# button.net
KiCad netlist of a schematic drawn in EAGLE
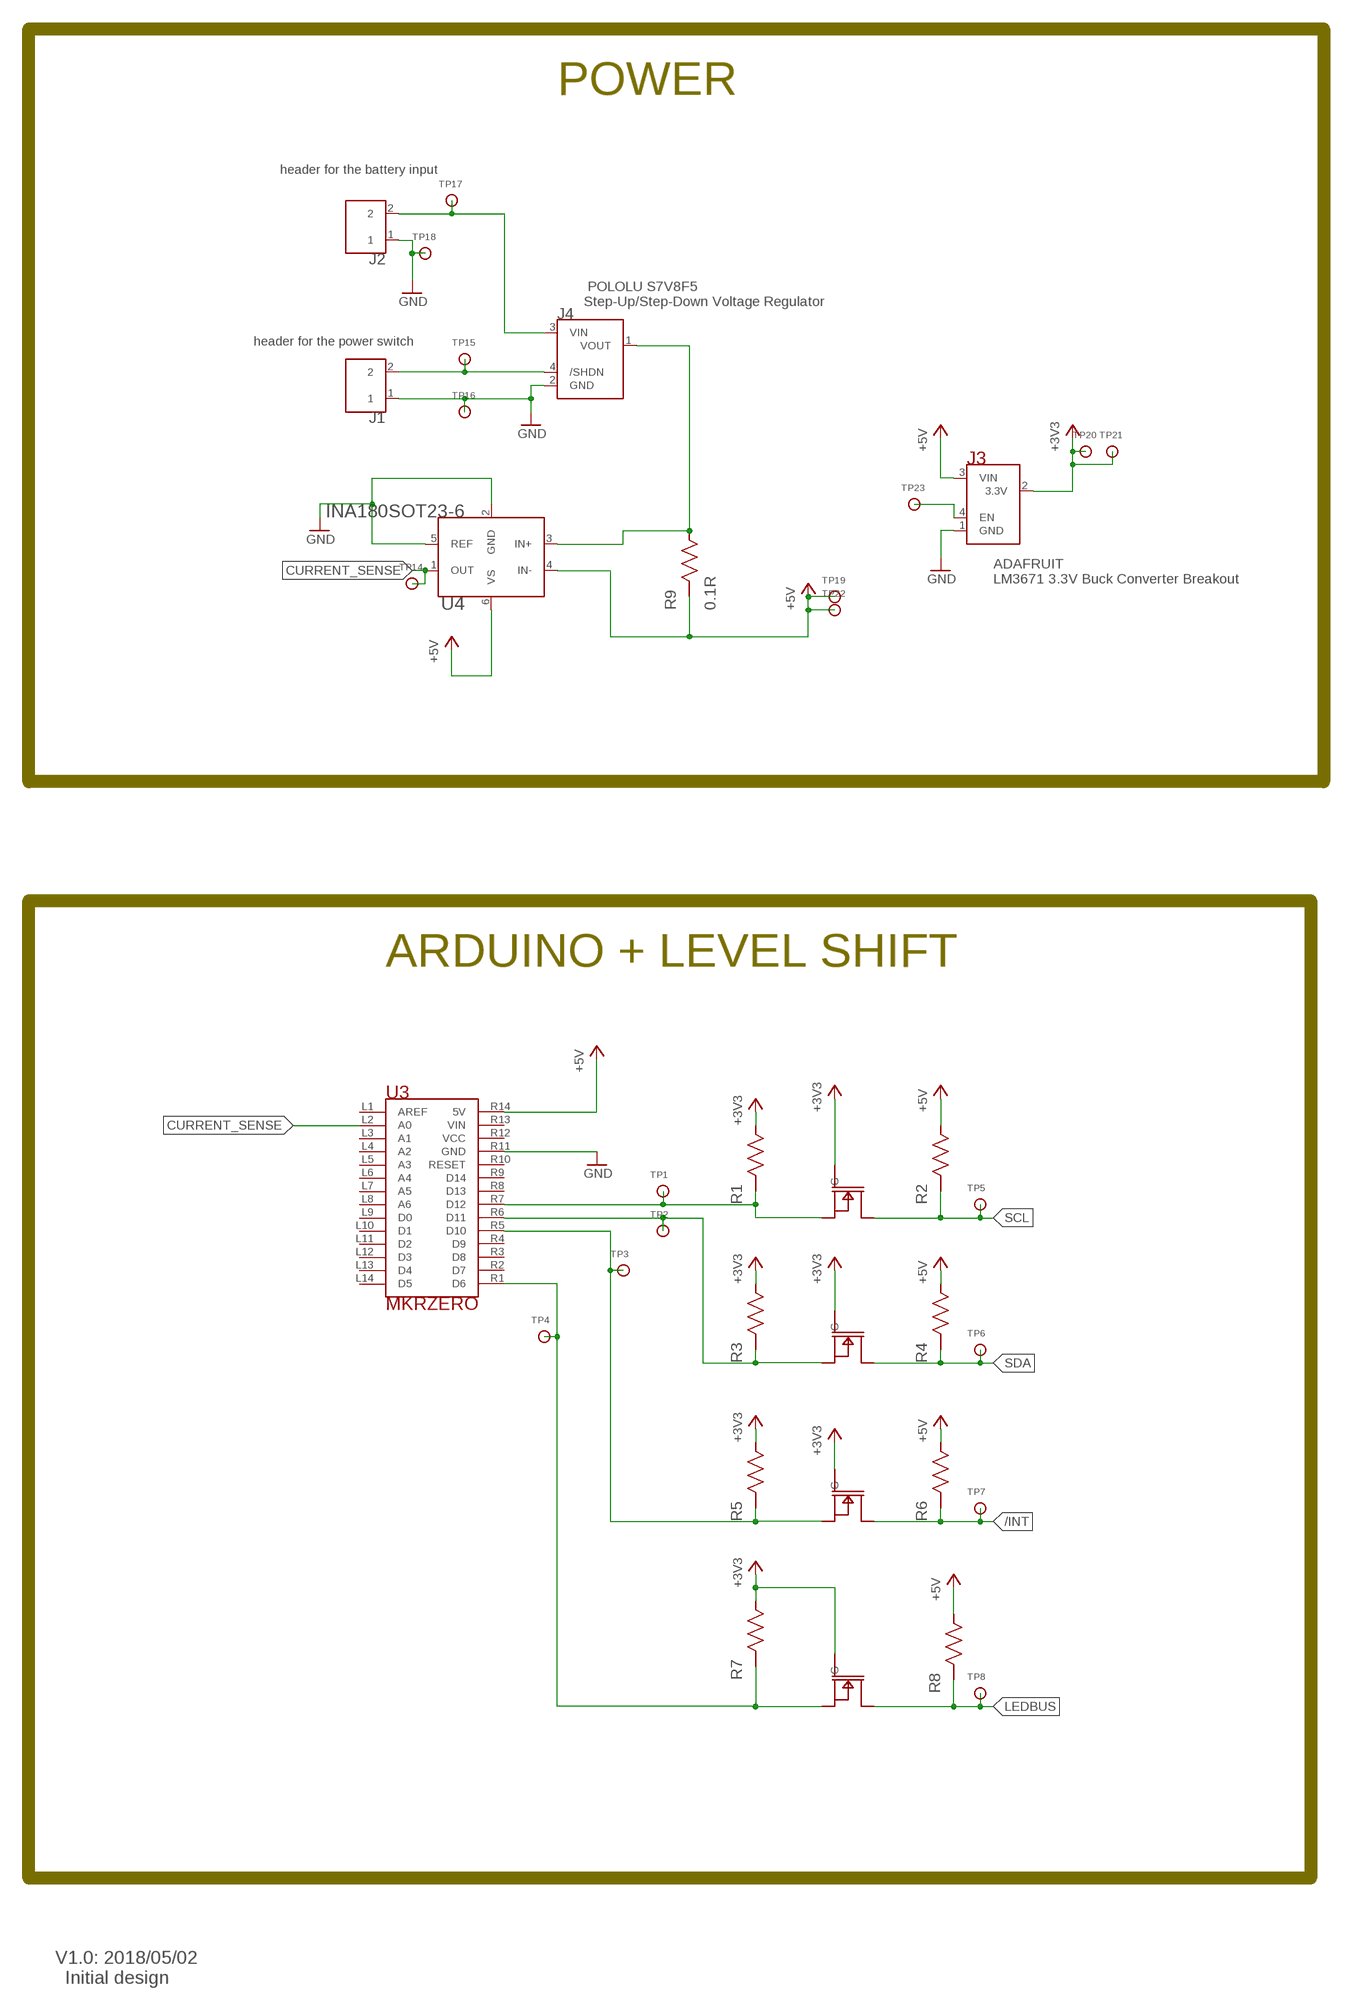
[diagram p0: schematic, sheet 1, part 1 of 2]
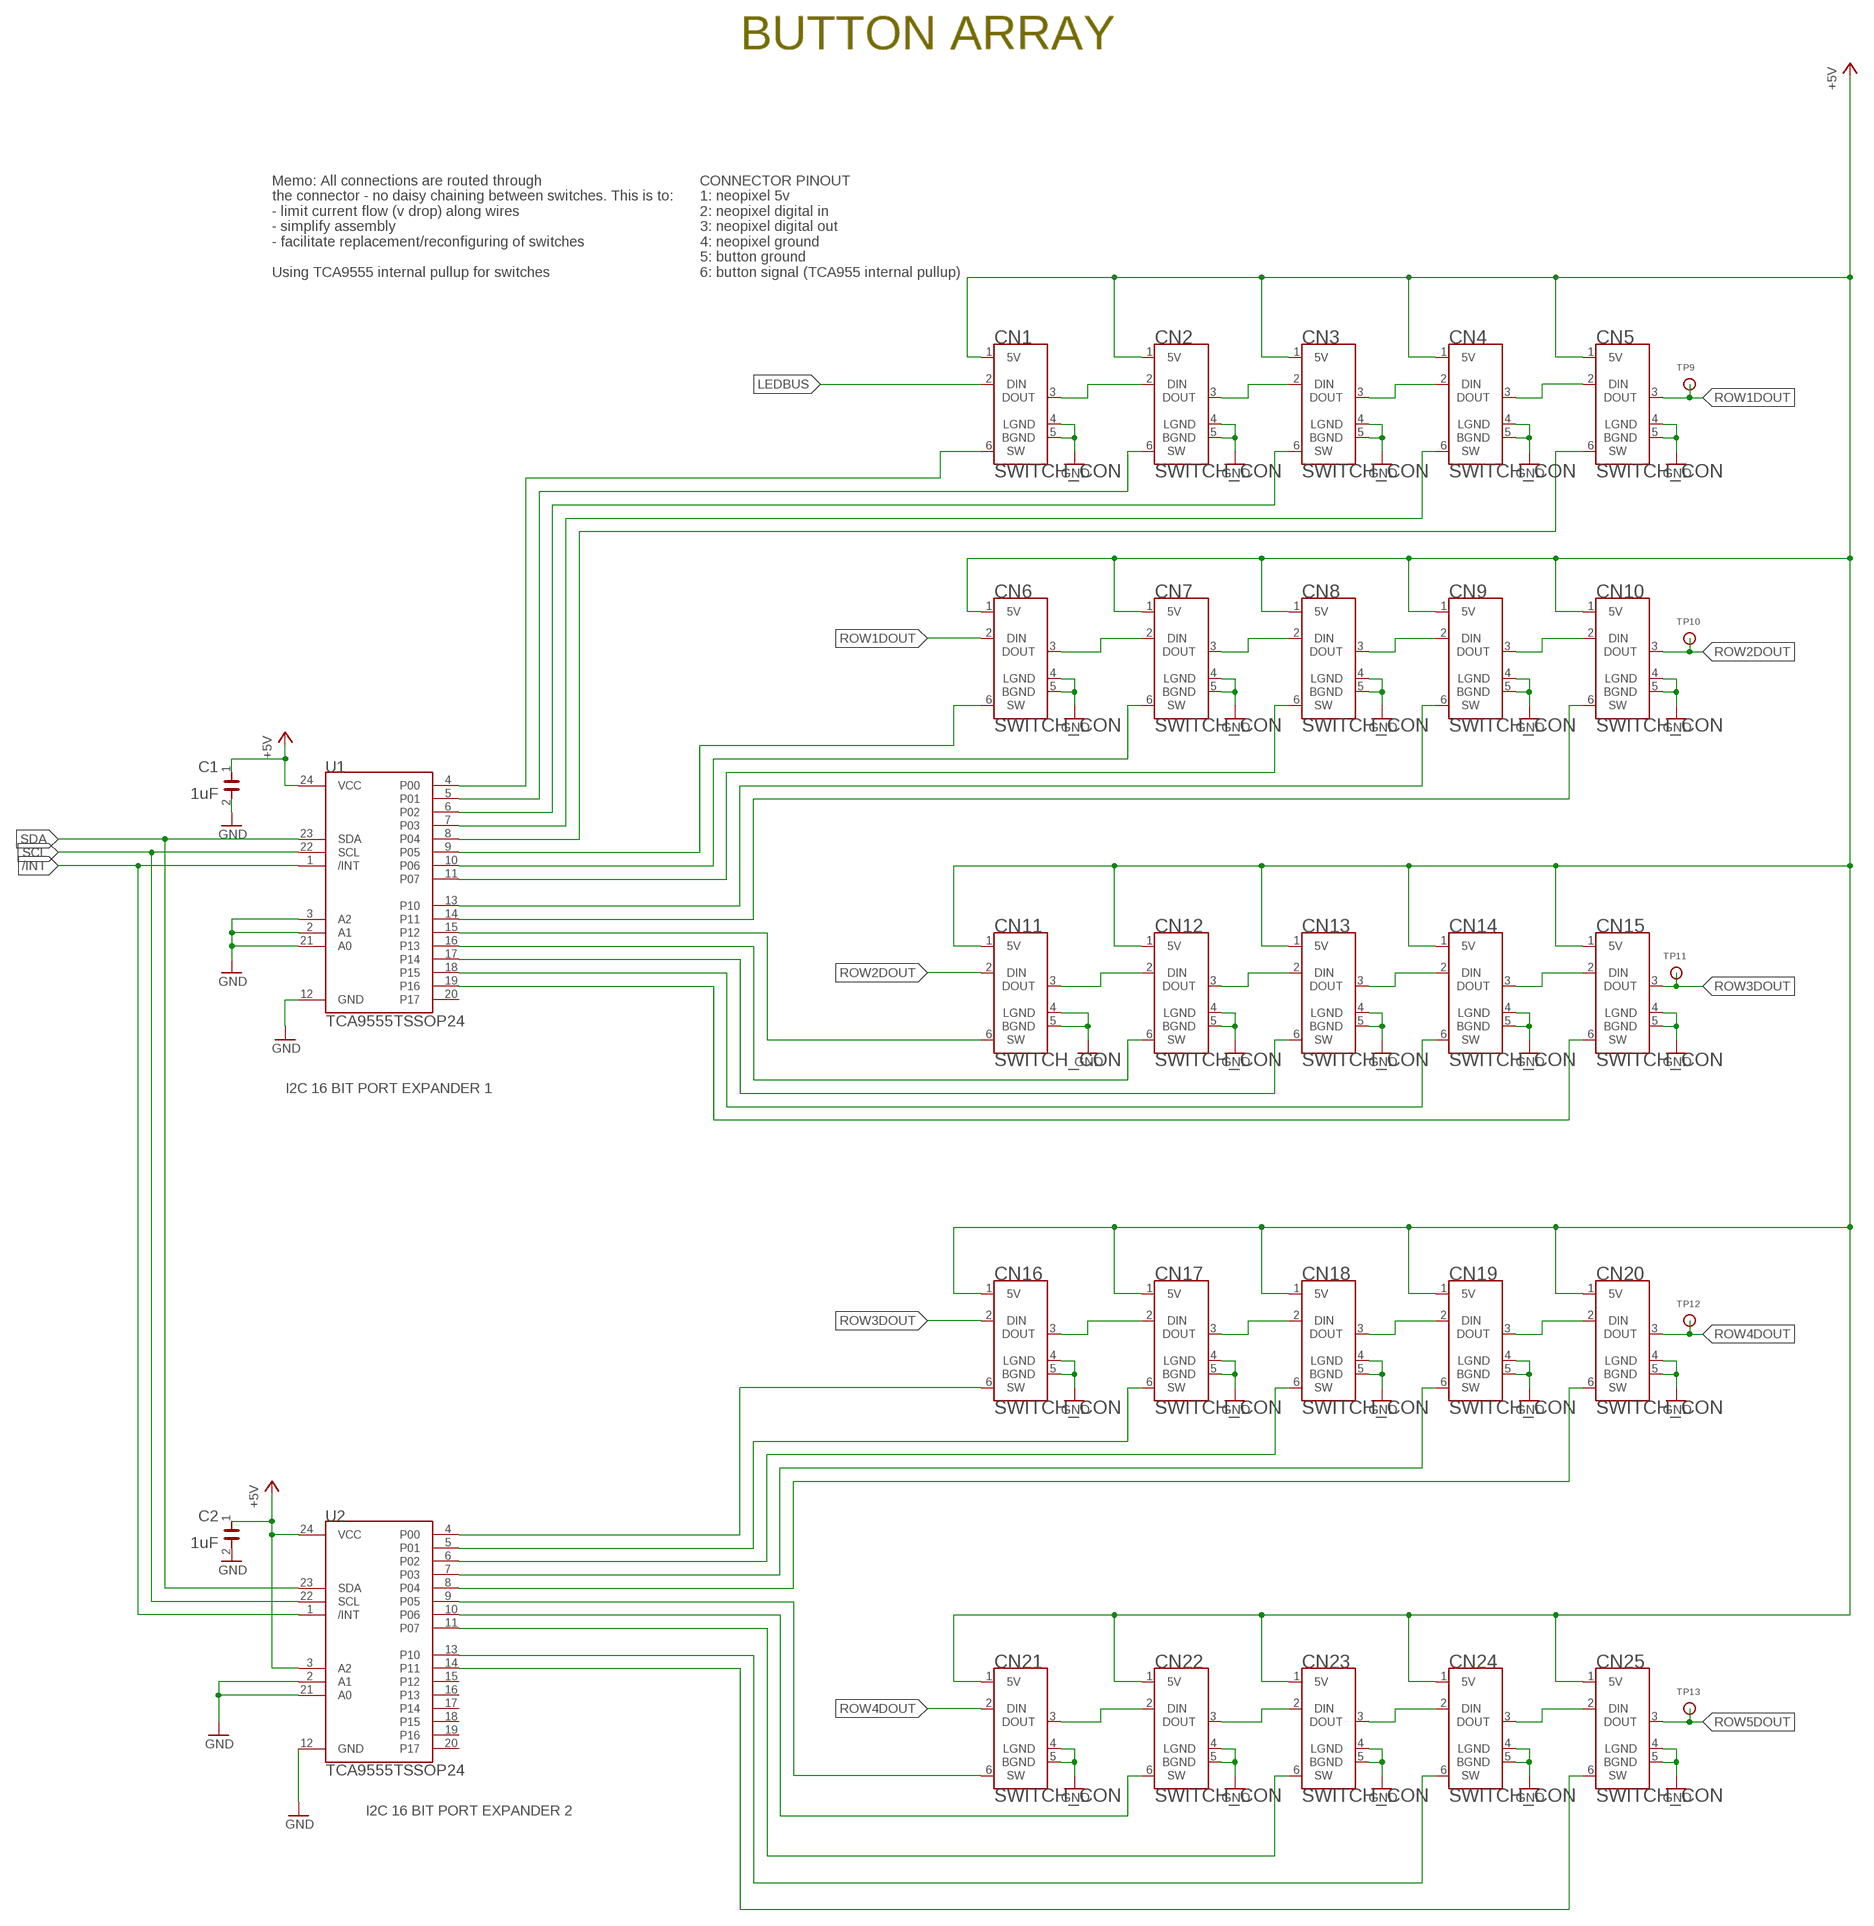
[diagram p1: schematic, sheet 1, part 2 of 2]

(export (version "E")
  (design (tool "Eeschema 10.0.6"))
  (components
    (comp (ref "C1")
      (value "1uF")
      (footprint "eagle-import:R0805")
      (libsource (lib "eagle-import") (part "CAPACITOR"))
    )
    (comp (ref "C2")
      (value "1uF")
      (footprint "eagle-import:R0805")
      (libsource (lib "eagle-import") (part "CAPACITOR"))
    )
    (comp (ref "CN1")
      (value "SWITCH_CON")
      (footprint "eagle-import:JST_XH6")
      (libsource (lib "eagle-import") (part "SWITCH_CON"))
    )
    (comp (ref "CN2")
      (value "SWITCH_CON")
      (footprint "eagle-import:JST_XH6")
      (libsource (lib "eagle-import") (part "SWITCH_CON"))
    )
    (comp (ref "CN3")
      (value "SWITCH_CON")
      (footprint "eagle-import:JST_XH6")
      (libsource (lib "eagle-import") (part "SWITCH_CON"))
    )
    (comp (ref "CN4")
      (value "SWITCH_CON")
      (footprint "eagle-import:JST_XH6")
      (libsource (lib "eagle-import") (part "SWITCH_CON"))
    )
    (comp (ref "CN5")
      (value "SWITCH_CON")
      (footprint "eagle-import:JST_XH6")
      (libsource (lib "eagle-import") (part "SWITCH_CON"))
    )
    (comp (ref "CN6")
      (value "SWITCH_CON")
      (footprint "eagle-import:JST_XH6")
      (libsource (lib "eagle-import") (part "SWITCH_CON"))
    )
    (comp (ref "CN7")
      (value "SWITCH_CON")
      (footprint "eagle-import:JST_XH6")
      (libsource (lib "eagle-import") (part "SWITCH_CON"))
    )
    (comp (ref "CN8")
      (value "SWITCH_CON")
      (footprint "eagle-import:JST_XH6")
      (libsource (lib "eagle-import") (part "SWITCH_CON"))
    )
    (comp (ref "CN9")
      (value "SWITCH_CON")
      (footprint "eagle-import:JST_XH6")
      (libsource (lib "eagle-import") (part "SWITCH_CON"))
    )
    (comp (ref "CN10")
      (value "SWITCH_CON")
      (footprint "eagle-import:JST_XH6")
      (libsource (lib "eagle-import") (part "SWITCH_CON"))
    )
    (comp (ref "CN11")
      (value "SWITCH_CON")
      (footprint "eagle-import:JST_XH6")
      (libsource (lib "eagle-import") (part "SWITCH_CON"))
    )
    (comp (ref "CN12")
      (value "SWITCH_CON")
      (footprint "eagle-import:JST_XH6")
      (libsource (lib "eagle-import") (part "SWITCH_CON"))
    )
    (comp (ref "CN13")
      (value "SWITCH_CON")
      (footprint "eagle-import:JST_XH6")
      (libsource (lib "eagle-import") (part "SWITCH_CON"))
    )
    (comp (ref "CN14")
      (value "SWITCH_CON")
      (footprint "eagle-import:JST_XH6")
      (libsource (lib "eagle-import") (part "SWITCH_CON"))
    )
    (comp (ref "CN15")
      (value "SWITCH_CON")
      (footprint "eagle-import:JST_XH6")
      (libsource (lib "eagle-import") (part "SWITCH_CON"))
    )
    (comp (ref "CN16")
      (value "SWITCH_CON")
      (footprint "eagle-import:JST_XH6")
      (libsource (lib "eagle-import") (part "SWITCH_CON"))
    )
    (comp (ref "CN17")
      (value "SWITCH_CON")
      (footprint "eagle-import:JST_XH6")
      (libsource (lib "eagle-import") (part "SWITCH_CON"))
    )
    (comp (ref "CN18")
      (value "SWITCH_CON")
      (footprint "eagle-import:JST_XH6")
      (libsource (lib "eagle-import") (part "SWITCH_CON"))
    )
    (comp (ref "CN19")
      (value "SWITCH_CON")
      (footprint "eagle-import:JST_XH6")
      (libsource (lib "eagle-import") (part "SWITCH_CON"))
    )
    (comp (ref "CN20")
      (value "SWITCH_CON")
      (footprint "eagle-import:JST_XH6")
      (libsource (lib "eagle-import") (part "SWITCH_CON"))
    )
    (comp (ref "CN21")
      (value "SWITCH_CON")
      (footprint "eagle-import:JST_XH6")
      (libsource (lib "eagle-import") (part "SWITCH_CON"))
    )
    (comp (ref "CN22")
      (value "SWITCH_CON")
      (footprint "eagle-import:JST_XH6")
      (libsource (lib "eagle-import") (part "SWITCH_CON"))
    )
    (comp (ref "CN23")
      (value "SWITCH_CON")
      (footprint "eagle-import:JST_XH6")
      (libsource (lib "eagle-import") (part "SWITCH_CON"))
    )
    (comp (ref "CN24")
      (value "SWITCH_CON")
      (footprint "eagle-import:JST_XH6")
      (libsource (lib "eagle-import") (part "SWITCH_CON"))
    )
    (comp (ref "CN25")
      (value "SWITCH_CON")
      (footprint "eagle-import:JST_XH6")
      (libsource (lib "eagle-import") (part "SWITCH_CON"))
    )
    (comp (ref "J1")
      (value "2WAY_JUMPER")
      (footprint "eagle-import:2PIN_HEADER")
      (libsource (lib "eagle-import") (part "2WAY_JUMPER"))
    )
    (comp (ref "J2")
      (value "2WAY_JUMPER")
      (footprint "eagle-import:2PIN_HEADER")
      (libsource (lib "eagle-import") (part "2WAY_JUMPER"))
    )
    (comp (ref "J3")
      (value "ADA-2745_3V3REG")
      (footprint "eagle-import:4PIN_HEADER")
      (libsource (lib "eagle-import") (part "ADA-2745_3V3REG"))
    )
    (comp (ref "J4")
      (value "S7V8F5")
      (footprint "eagle-import:4PIN_HEADER")
      (libsource (lib "eagle-import") (part "S7V8F5"))
    )
    (comp (ref "Q1")
      (value "BSS138SOT23")
      (footprint "eagle-import:SOT23")
      (libsource (lib "eagle-import") (part "BSS138SOT23"))
    )
    (comp (ref "Q2")
      (value "BSS138SOT23")
      (footprint "eagle-import:SOT23")
      (libsource (lib "eagle-import") (part "BSS138SOT23"))
    )
    (comp (ref "Q3")
      (value "BSS138SOT23")
      (footprint "eagle-import:SOT23")
      (libsource (lib "eagle-import") (part "BSS138SOT23"))
    )
    (comp (ref "Q4")
      (value "BSS138SOT23")
      (footprint "eagle-import:SOT23")
      (libsource (lib "eagle-import") (part "BSS138SOT23"))
    )
    (comp (ref "R1")
      (value "RESISTOR8085")
      (footprint "eagle-import:R0805")
      (libsource (lib "eagle-import") (part "RESISTOR8085"))
    )
    (comp (ref "R2")
      (value "RESISTOR8085")
      (footprint "eagle-import:R0805")
      (libsource (lib "eagle-import") (part "RESISTOR8085"))
    )
    (comp (ref "R3")
      (value "RESISTOR8085")
      (footprint "eagle-import:R0805")
      (libsource (lib "eagle-import") (part "RESISTOR8085"))
    )
    (comp (ref "R4")
      (value "RESISTOR8085")
      (footprint "eagle-import:R0805")
      (libsource (lib "eagle-import") (part "RESISTOR8085"))
    )
    (comp (ref "R5")
      (value "RESISTOR8085")
      (footprint "eagle-import:R0805")
      (libsource (lib "eagle-import") (part "RESISTOR8085"))
    )
    (comp (ref "R6")
      (value "RESISTOR8085")
      (footprint "eagle-import:R0805")
      (libsource (lib "eagle-import") (part "RESISTOR8085"))
    )
    (comp (ref "R7")
      (value "RESISTOR8085")
      (footprint "eagle-import:R0805")
      (libsource (lib "eagle-import") (part "RESISTOR8085"))
    )
    (comp (ref "R8")
      (value "RESISTOR8085")
      (footprint "eagle-import:R0805")
      (libsource (lib "eagle-import") (part "RESISTOR8085"))
    )
    (comp (ref "R9")
      (value "0.1R")
      (footprint "eagle-import:R1206")
      (libsource (lib "eagle-import") (part "PT1206FR-070R1L1206"))
    )
    (comp (ref "TP1")
      (value "TEST_POINT")
      (footprint "eagle-import:TESTPAD_2MM")
      (libsource (lib "eagle-import") (part "TEST_POINT"))
    )
    (comp (ref "TP2")
      (value "TEST_POINT")
      (footprint "eagle-import:TESTPAD_2MM")
      (libsource (lib "eagle-import") (part "TEST_POINT"))
    )
    (comp (ref "TP3")
      (value "TEST_POINT")
      (footprint "eagle-import:TESTPAD_2MM")
      (libsource (lib "eagle-import") (part "TEST_POINT"))
    )
    (comp (ref "TP4")
      (value "TEST_POINT")
      (footprint "eagle-import:TESTPAD_2MM")
      (libsource (lib "eagle-import") (part "TEST_POINT"))
    )
    (comp (ref "TP5")
      (value "TEST_POINT")
      (footprint "eagle-import:TESTPAD_2MM")
      (libsource (lib "eagle-import") (part "TEST_POINT"))
    )
    (comp (ref "TP6")
      (value "TEST_POINT")
      (footprint "eagle-import:TESTPAD_2MM")
      (libsource (lib "eagle-import") (part "TEST_POINT"))
    )
    (comp (ref "TP7")
      (value "TEST_POINT")
      (footprint "eagle-import:TESTPAD_2MM")
      (libsource (lib "eagle-import") (part "TEST_POINT"))
    )
    (comp (ref "TP8")
      (value "TEST_POINT")
      (footprint "eagle-import:TESTPAD_2MM")
      (libsource (lib "eagle-import") (part "TEST_POINT"))
    )
    (comp (ref "TP9")
      (value "TEST_POINT")
      (footprint "eagle-import:TESTPAD_2MM")
      (libsource (lib "eagle-import") (part "TEST_POINT"))
    )
    (comp (ref "TP10")
      (value "TEST_POINT")
      (footprint "eagle-import:TESTPAD_2MM")
      (libsource (lib "eagle-import") (part "TEST_POINT"))
    )
    (comp (ref "TP11")
      (value "TEST_POINT")
      (footprint "eagle-import:TESTPAD_2MM")
      (libsource (lib "eagle-import") (part "TEST_POINT"))
    )
    (comp (ref "TP12")
      (value "TEST_POINT")
      (footprint "eagle-import:TESTPAD_2MM")
      (libsource (lib "eagle-import") (part "TEST_POINT"))
    )
    (comp (ref "TP13")
      (value "TEST_POINT")
      (footprint "eagle-import:TESTPAD_2MM")
      (libsource (lib "eagle-import") (part "TEST_POINT"))
    )
    (comp (ref "TP14")
      (value "TEST_POINT")
      (footprint "eagle-import:TESTPAD_2MM")
      (libsource (lib "eagle-import") (part "TEST_POINT"))
    )
    (comp (ref "TP15")
      (value "TEST_POINT")
      (footprint "eagle-import:TESTPAD_2MM")
      (libsource (lib "eagle-import") (part "TEST_POINT"))
    )
    (comp (ref "TP16")
      (value "TEST_POINT")
      (footprint "eagle-import:TESTPAD_2MM")
      (libsource (lib "eagle-import") (part "TEST_POINT"))
    )
    (comp (ref "TP17")
      (value "TEST_POINT")
      (footprint "eagle-import:TESTPAD_2MM")
      (libsource (lib "eagle-import") (part "TEST_POINT"))
    )
    (comp (ref "TP18")
      (value "TEST_POINT")
      (footprint "eagle-import:TESTPAD_2MM")
      (libsource (lib "eagle-import") (part "TEST_POINT"))
    )
    (comp (ref "TP19")
      (value "TEST_POINT")
      (footprint "eagle-import:TESTPAD_2MM")
      (libsource (lib "eagle-import") (part "TEST_POINT"))
    )
    (comp (ref "TP20")
      (value "TEST_POINT")
      (footprint "eagle-import:TESTPAD_2MM")
      (libsource (lib "eagle-import") (part "TEST_POINT"))
    )
    (comp (ref "TP21")
      (value "TEST_POINT")
      (footprint "eagle-import:TESTPAD_2MM")
      (libsource (lib "eagle-import") (part "TEST_POINT"))
    )
    (comp (ref "TP22")
      (value "TEST_POINT")
      (footprint "eagle-import:TESTPAD_2MM")
      (libsource (lib "eagle-import") (part "TEST_POINT"))
    )
    (comp (ref "TP23")
      (value "TEST_POINT")
      (footprint "eagle-import:TESTPAD_2MM")
      (libsource (lib "eagle-import") (part "TEST_POINT"))
    )
    (comp (ref "U1")
      (value "TCA9555TSSOP24")
      (footprint "eagle-import:SOP65P640X120-24")
      (libsource (lib "eagle-import") (part "TCA9555TSSOP24"))
    )
    (comp (ref "U2")
      (value "TCA9555TSSOP24")
      (footprint "eagle-import:SOP65P640X120-24")
      (libsource (lib "eagle-import") (part "TCA9555TSSOP24"))
    )
    (comp (ref "U3")
      (value "MKRZERO")
      (footprint "eagle-import:ARDUINO_MKR")
      (libsource (lib "eagle-import") (part "ATMEL_MLRZERO"))
    )
    (comp (ref "U4")
      (value "INA180SOT23-6")
      (footprint "eagle-import:SOT95P290X145-6")
      (libsource (lib "eagle-import") (part "INA180SOT23-6"))
    )
  )
  (nets
    (net (code "1") (name "+3V3") (class "Default")
      (node (ref "J3") (pin "2") (pinfunction "3.3V_2") (pintype "bidirectional"))
      (node (ref "Q1") (pin "1") (pinfunction "G_1") (pintype "bidirectional"))
      (node (ref "Q2") (pin "1") (pinfunction "G_1") (pintype "bidirectional"))
      (node (ref "Q3") (pin "1") (pinfunction "G_1") (pintype "bidirectional"))
      (node (ref "Q4") (pin "1") (pinfunction "G_1") (pintype "bidirectional"))
      (node (ref "R1") (pin "2") (pinfunction "P$2_2") (pintype "bidirectional"))
      (node (ref "R3") (pin "2") (pinfunction "P$2_2") (pintype "bidirectional"))
      (node (ref "R5") (pin "2") (pinfunction "P$2_2") (pintype "bidirectional"))
      (node (ref "R7") (pin "2") (pinfunction "P$2_2") (pintype "bidirectional"))
      (node (ref "TP20") (pin "P$1") (pinfunction "1_P$1") (pintype "bidirectional"))
      (node (ref "TP21") (pin "P$1") (pinfunction "1_P$1") (pintype "bidirectional"))
    )
    (net (code "2") (name "+5V") (class "Default")
      (node (ref "C1") (pin "1") (pinfunction "P$1_1") (pintype "bidirectional"))
      (node (ref "C2") (pin "1") (pinfunction "P$1_1") (pintype "bidirectional"))
      (node (ref "CN1") (pin "1") (pinfunction "5V_1") (pintype "bidirectional"))
      (node (ref "CN10") (pin "1") (pinfunction "5V_1") (pintype "bidirectional"))
      (node (ref "CN11") (pin "1") (pinfunction "5V_1") (pintype "bidirectional"))
      (node (ref "CN12") (pin "1") (pinfunction "5V_1") (pintype "bidirectional"))
      (node (ref "CN13") (pin "1") (pinfunction "5V_1") (pintype "bidirectional"))
      (node (ref "CN14") (pin "1") (pinfunction "5V_1") (pintype "bidirectional"))
      (node (ref "CN15") (pin "1") (pinfunction "5V_1") (pintype "bidirectional"))
      (node (ref "CN16") (pin "1") (pinfunction "5V_1") (pintype "bidirectional"))
      (node (ref "CN17") (pin "1") (pinfunction "5V_1") (pintype "bidirectional"))
      (node (ref "CN18") (pin "1") (pinfunction "5V_1") (pintype "bidirectional"))
      (node (ref "CN19") (pin "1") (pinfunction "5V_1") (pintype "bidirectional"))
      (node (ref "CN2") (pin "1") (pinfunction "5V_1") (pintype "bidirectional"))
      (node (ref "CN20") (pin "1") (pinfunction "5V_1") (pintype "bidirectional"))
      (node (ref "CN21") (pin "1") (pinfunction "5V_1") (pintype "bidirectional"))
      (node (ref "CN22") (pin "1") (pinfunction "5V_1") (pintype "bidirectional"))
      (node (ref "CN23") (pin "1") (pinfunction "5V_1") (pintype "bidirectional"))
      (node (ref "CN24") (pin "1") (pinfunction "5V_1") (pintype "bidirectional"))
      (node (ref "CN25") (pin "1") (pinfunction "5V_1") (pintype "bidirectional"))
      (node (ref "CN3") (pin "1") (pinfunction "5V_1") (pintype "bidirectional"))
      (node (ref "CN4") (pin "1") (pinfunction "5V_1") (pintype "bidirectional"))
      (node (ref "CN5") (pin "1") (pinfunction "5V_1") (pintype "bidirectional"))
      (node (ref "CN6") (pin "1") (pinfunction "5V_1") (pintype "bidirectional"))
      (node (ref "CN7") (pin "1") (pinfunction "5V_1") (pintype "bidirectional"))
      (node (ref "CN8") (pin "1") (pinfunction "5V_1") (pintype "bidirectional"))
      (node (ref "CN9") (pin "1") (pinfunction "5V_1") (pintype "bidirectional"))
      (node (ref "J3") (pin "3") (pinfunction "VIN_3") (pintype "bidirectional"))
      (node (ref "R2") (pin "2") (pinfunction "P$2_2") (pintype "bidirectional"))
      (node (ref "R4") (pin "2") (pinfunction "P$2_2") (pintype "bidirectional"))
      (node (ref "R6") (pin "2") (pinfunction "P$2_2") (pintype "bidirectional"))
      (node (ref "R8") (pin "2") (pinfunction "P$2_2") (pintype "bidirectional"))
      (node (ref "R9") (pin "1") (pinfunction "P$1_1") (pintype "bidirectional"))
      (node (ref "TP19") (pin "P$1") (pinfunction "1_P$1") (pintype "bidirectional"))
      (node (ref "TP22") (pin "P$1") (pinfunction "1_P$1") (pintype "bidirectional"))
      (node (ref "U1") (pin "24") (pinfunction "VCC_24") (pintype "bidirectional"))
      (node (ref "U2") (pin "24") (pinfunction "VCC_24") (pintype "bidirectional"))
      (node (ref "U2") (pin "3") (pinfunction "A2_3") (pintype "bidirectional"))
      (node (ref "U3") (pin "R14") (pinfunction "5V_R14") (pintype "bidirectional"))
      (node (ref "U4") (pin "4") (pinfunction "IN-_4") (pintype "bidirectional"))
      (node (ref "U4") (pin "6") (pinfunction "VS_6") (pintype "power_in"))
    )
    (net (code "3") (name "CURRENT_SENSE") (class "Default")
      (node (ref "TP14") (pin "P$1") (pinfunction "1_P$1") (pintype "bidirectional"))
      (node (ref "U3") (pin "L2") (pinfunction "A0_L2") (pintype "bidirectional"))
      (node (ref "U4") (pin "1") (pinfunction "OUT_1") (pintype "bidirectional"))
    )
    (net (code "4") (name "GND") (class "Default")
      (node (ref "C1") (pin "2") (pinfunction "P$2_2") (pintype "bidirectional"))
      (node (ref "C2") (pin "2") (pinfunction "P$2_2") (pintype "bidirectional"))
      (node (ref "CN1") (pin "4") (pinfunction "LGND_4") (pintype "bidirectional"))
      (node (ref "CN1") (pin "5") (pinfunction "BGND_5") (pintype "bidirectional"))
      (node (ref "CN10") (pin "4") (pinfunction "LGND_4") (pintype "bidirectional"))
      (node (ref "CN10") (pin "5") (pinfunction "BGND_5") (pintype "bidirectional"))
      (node (ref "CN11") (pin "4") (pinfunction "LGND_4") (pintype "bidirectional"))
      (node (ref "CN11") (pin "5") (pinfunction "BGND_5") (pintype "bidirectional"))
      (node (ref "CN12") (pin "4") (pinfunction "LGND_4") (pintype "bidirectional"))
      (node (ref "CN12") (pin "5") (pinfunction "BGND_5") (pintype "bidirectional"))
      (node (ref "CN13") (pin "4") (pinfunction "LGND_4") (pintype "bidirectional"))
      (node (ref "CN13") (pin "5") (pinfunction "BGND_5") (pintype "bidirectional"))
      (node (ref "CN14") (pin "4") (pinfunction "LGND_4") (pintype "bidirectional"))
      (node (ref "CN14") (pin "5") (pinfunction "BGND_5") (pintype "bidirectional"))
      (node (ref "CN15") (pin "4") (pinfunction "LGND_4") (pintype "bidirectional"))
      (node (ref "CN15") (pin "5") (pinfunction "BGND_5") (pintype "bidirectional"))
      (node (ref "CN16") (pin "4") (pinfunction "LGND_4") (pintype "bidirectional"))
      (node (ref "CN16") (pin "5") (pinfunction "BGND_5") (pintype "bidirectional"))
      (node (ref "CN17") (pin "4") (pinfunction "LGND_4") (pintype "bidirectional"))
      (node (ref "CN17") (pin "5") (pinfunction "BGND_5") (pintype "bidirectional"))
      (node (ref "CN18") (pin "4") (pinfunction "LGND_4") (pintype "bidirectional"))
      (node (ref "CN18") (pin "5") (pinfunction "BGND_5") (pintype "bidirectional"))
      (node (ref "CN19") (pin "4") (pinfunction "LGND_4") (pintype "bidirectional"))
      (node (ref "CN19") (pin "5") (pinfunction "BGND_5") (pintype "bidirectional"))
      (node (ref "CN2") (pin "4") (pinfunction "LGND_4") (pintype "bidirectional"))
      (node (ref "CN2") (pin "5") (pinfunction "BGND_5") (pintype "bidirectional"))
      (node (ref "CN20") (pin "4") (pinfunction "LGND_4") (pintype "bidirectional"))
      (node (ref "CN20") (pin "5") (pinfunction "BGND_5") (pintype "bidirectional"))
      (node (ref "CN21") (pin "4") (pinfunction "LGND_4") (pintype "bidirectional"))
      (node (ref "CN21") (pin "5") (pinfunction "BGND_5") (pintype "bidirectional"))
      (node (ref "CN22") (pin "4") (pinfunction "LGND_4") (pintype "bidirectional"))
      (node (ref "CN22") (pin "5") (pinfunction "BGND_5") (pintype "bidirectional"))
      (node (ref "CN23") (pin "4") (pinfunction "LGND_4") (pintype "bidirectional"))
      (node (ref "CN23") (pin "5") (pinfunction "BGND_5") (pintype "bidirectional"))
      (node (ref "CN24") (pin "4") (pinfunction "LGND_4") (pintype "bidirectional"))
      (node (ref "CN24") (pin "5") (pinfunction "BGND_5") (pintype "bidirectional"))
      (node (ref "CN25") (pin "4") (pinfunction "LGND_4") (pintype "bidirectional"))
      (node (ref "CN25") (pin "5") (pinfunction "BGND_5") (pintype "bidirectional"))
      (node (ref "CN3") (pin "4") (pinfunction "LGND_4") (pintype "bidirectional"))
      (node (ref "CN3") (pin "5") (pinfunction "BGND_5") (pintype "bidirectional"))
      (node (ref "CN4") (pin "4") (pinfunction "LGND_4") (pintype "bidirectional"))
      (node (ref "CN4") (pin "5") (pinfunction "BGND_5") (pintype "bidirectional"))
      (node (ref "CN5") (pin "4") (pinfunction "LGND_4") (pintype "bidirectional"))
      (node (ref "CN5") (pin "5") (pinfunction "BGND_5") (pintype "bidirectional"))
      (node (ref "CN6") (pin "4") (pinfunction "LGND_4") (pintype "bidirectional"))
      (node (ref "CN6") (pin "5") (pinfunction "BGND_5") (pintype "bidirectional"))
      (node (ref "CN7") (pin "4") (pinfunction "LGND_4") (pintype "bidirectional"))
      (node (ref "CN7") (pin "5") (pinfunction "BGND_5") (pintype "bidirectional"))
      (node (ref "CN8") (pin "4") (pinfunction "LGND_4") (pintype "bidirectional"))
      (node (ref "CN8") (pin "5") (pinfunction "BGND_5") (pintype "bidirectional"))
      (node (ref "CN9") (pin "4") (pinfunction "LGND_4") (pintype "bidirectional"))
      (node (ref "CN9") (pin "5") (pinfunction "BGND_5") (pintype "bidirectional"))
      (node (ref "J1") (pin "1") (pinfunction "1_1") (pintype "bidirectional"))
      (node (ref "J2") (pin "1") (pinfunction "1_1") (pintype "bidirectional"))
      (node (ref "J3") (pin "1") (pinfunction "GND_1") (pintype "bidirectional"))
      (node (ref "J4") (pin "2") (pinfunction "GND_2") (pintype "bidirectional"))
      (node (ref "TP16") (pin "P$1") (pinfunction "1_P$1") (pintype "bidirectional"))
      (node (ref "TP18") (pin "P$1") (pinfunction "1_P$1") (pintype "bidirectional"))
      (node (ref "U1") (pin "12") (pinfunction "GND_12") (pintype "bidirectional"))
      (node (ref "U1") (pin "2") (pinfunction "A1_2") (pintype "bidirectional"))
      (node (ref "U1") (pin "21") (pinfunction "A0_21") (pintype "bidirectional"))
      (node (ref "U1") (pin "3") (pinfunction "A2_3") (pintype "bidirectional"))
      (node (ref "U2") (pin "12") (pinfunction "GND_12") (pintype "bidirectional"))
      (node (ref "U2") (pin "2") (pinfunction "A1_2") (pintype "bidirectional"))
      (node (ref "U2") (pin "21") (pinfunction "A0_21") (pintype "bidirectional"))
      (node (ref "U3") (pin "R11") (pinfunction "GND_R11") (pintype "bidirectional"))
      (node (ref "U4") (pin "2") (pinfunction "GND_2") (pintype "bidirectional"))
      (node (ref "U4") (pin "5") (pinfunction "REF_5") (pintype "bidirectional"))
    )
    (net (code "5") (name "LEDBUS") (class "Default")
      (node (ref "CN1") (pin "2") (pinfunction "DIN_2") (pintype "bidirectional"))
      (node (ref "Q4") (pin "3") (pinfunction "D_3") (pintype "bidirectional"))
      (node (ref "R8") (pin "1") (pinfunction "P$1_1") (pintype "bidirectional"))
      (node (ref "TP8") (pin "P$1") (pinfunction "1_P$1") (pintype "bidirectional"))
    )
    (net (code "6") (name "Net-(CN1-DOUT)") (class "Default")
      (node (ref "CN1") (pin "3") (pinfunction "DOUT_3") (pintype "bidirectional"))
      (node (ref "CN2") (pin "2") (pinfunction "DIN_2") (pintype "bidirectional"))
    )
    (net (code "7") (name "Net-(CN1-SW)") (class "Default")
      (node (ref "CN1") (pin "6") (pinfunction "SW_6") (pintype "bidirectional"))
      (node (ref "U1") (pin "4") (pinfunction "P00_4") (pintype "bidirectional"))
    )
    (net (code "8") (name "Net-(CN2-DOUT)") (class "Default")
      (node (ref "CN2") (pin "3") (pinfunction "DOUT_3") (pintype "bidirectional"))
      (node (ref "CN3") (pin "2") (pinfunction "DIN_2") (pintype "bidirectional"))
    )
    (net (code "9") (name "Net-(CN2-SW)") (class "Default")
      (node (ref "CN2") (pin "6") (pinfunction "SW_6") (pintype "bidirectional"))
      (node (ref "U1") (pin "5") (pinfunction "P01_5") (pintype "bidirectional"))
    )
    (net (code "10") (name "Net-(CN3-DOUT)") (class "Default")
      (node (ref "CN3") (pin "3") (pinfunction "DOUT_3") (pintype "bidirectional"))
      (node (ref "CN4") (pin "2") (pinfunction "DIN_2") (pintype "bidirectional"))
    )
    (net (code "11") (name "Net-(CN3-SW)") (class "Default")
      (node (ref "CN3") (pin "6") (pinfunction "SW_6") (pintype "bidirectional"))
      (node (ref "U1") (pin "6") (pinfunction "P02_6") (pintype "bidirectional"))
    )
    (net (code "12") (name "Net-(CN4-DOUT)") (class "Default")
      (node (ref "CN4") (pin "3") (pinfunction "DOUT_3") (pintype "bidirectional"))
      (node (ref "CN5") (pin "2") (pinfunction "DIN_2") (pintype "bidirectional"))
    )
    (net (code "13") (name "Net-(CN4-SW)") (class "Default")
      (node (ref "CN4") (pin "6") (pinfunction "SW_6") (pintype "bidirectional"))
      (node (ref "U1") (pin "7") (pinfunction "P03_7") (pintype "bidirectional"))
    )
    (net (code "14") (name "Net-(CN5-SW)") (class "Default")
      (node (ref "CN5") (pin "6") (pinfunction "SW_6") (pintype "bidirectional"))
      (node (ref "U1") (pin "8") (pinfunction "P04_8") (pintype "bidirectional"))
    )
    (net (code "15") (name "Net-(CN6-DOUT)") (class "Default")
      (node (ref "CN6") (pin "3") (pinfunction "DOUT_3") (pintype "bidirectional"))
      (node (ref "CN7") (pin "2") (pinfunction "DIN_2") (pintype "bidirectional"))
    )
    (net (code "16") (name "Net-(CN6-SW)") (class "Default")
      (node (ref "CN6") (pin "6") (pinfunction "SW_6") (pintype "bidirectional"))
      (node (ref "U1") (pin "9") (pinfunction "P05_9") (pintype "bidirectional"))
    )
    (net (code "17") (name "Net-(CN7-DOUT)") (class "Default")
      (node (ref "CN7") (pin "3") (pinfunction "DOUT_3") (pintype "bidirectional"))
      (node (ref "CN8") (pin "2") (pinfunction "DIN_2") (pintype "bidirectional"))
    )
    (net (code "18") (name "Net-(CN7-SW)") (class "Default")
      (node (ref "CN7") (pin "6") (pinfunction "SW_6") (pintype "bidirectional"))
      (node (ref "U1") (pin "10") (pinfunction "P06_10") (pintype "bidirectional"))
    )
    (net (code "19") (name "Net-(CN8-DOUT)") (class "Default")
      (node (ref "CN8") (pin "3") (pinfunction "DOUT_3") (pintype "bidirectional"))
      (node (ref "CN9") (pin "2") (pinfunction "DIN_2") (pintype "bidirectional"))
    )
    (net (code "20") (name "Net-(CN8-SW)") (class "Default")
      (node (ref "CN8") (pin "6") (pinfunction "SW_6") (pintype "bidirectional"))
      (node (ref "U1") (pin "11") (pinfunction "P07_11") (pintype "bidirectional"))
    )
    (net (code "21") (name "Net-(CN9-SW)") (class "Default")
      (node (ref "CN9") (pin "6") (pinfunction "SW_6") (pintype "bidirectional"))
      (node (ref "U1") (pin "13") (pinfunction "P10_13") (pintype "bidirectional"))
    )
    (net (code "22") (name "Net-(CN10-DIN)") (class "Default")
      (node (ref "CN10") (pin "2") (pinfunction "DIN_2") (pintype "bidirectional"))
      (node (ref "CN9") (pin "3") (pinfunction "DOUT_3") (pintype "bidirectional"))
    )
    (net (code "23") (name "Net-(CN10-SW)") (class "Default")
      (node (ref "CN10") (pin "6") (pinfunction "SW_6") (pintype "bidirectional"))
      (node (ref "U1") (pin "14") (pinfunction "P11_14") (pintype "bidirectional"))
    )
    (net (code "24") (name "Net-(CN11-DOUT)") (class "Default")
      (node (ref "CN11") (pin "3") (pinfunction "DOUT_3") (pintype "bidirectional"))
      (node (ref "CN12") (pin "2") (pinfunction "DIN_2") (pintype "bidirectional"))
    )
    (net (code "25") (name "Net-(CN11-SW)") (class "Default")
      (node (ref "CN11") (pin "6") (pinfunction "SW_6") (pintype "bidirectional"))
      (node (ref "U1") (pin "15") (pinfunction "P12_15") (pintype "bidirectional"))
    )
    (net (code "26") (name "Net-(CN12-DOUT)") (class "Default")
      (node (ref "CN12") (pin "3") (pinfunction "DOUT_3") (pintype "bidirectional"))
      (node (ref "CN13") (pin "2") (pinfunction "DIN_2") (pintype "bidirectional"))
    )
    (net (code "27") (name "Net-(CN12-SW)") (class "Default")
      (node (ref "CN12") (pin "6") (pinfunction "SW_6") (pintype "bidirectional"))
      (node (ref "U1") (pin "16") (pinfunction "P13_16") (pintype "bidirectional"))
    )
    (net (code "28") (name "Net-(CN13-DOUT)") (class "Default")
      (node (ref "CN13") (pin "3") (pinfunction "DOUT_3") (pintype "bidirectional"))
      (node (ref "CN14") (pin "2") (pinfunction "DIN_2") (pintype "bidirectional"))
    )
    (net (code "29") (name "Net-(CN13-SW)") (class "Default")
      (node (ref "CN13") (pin "6") (pinfunction "SW_6") (pintype "bidirectional"))
      (node (ref "U1") (pin "17") (pinfunction "P14_17") (pintype "bidirectional"))
    )
    (net (code "30") (name "Net-(CN14-DOUT)") (class "Default")
      (node (ref "CN14") (pin "3") (pinfunction "DOUT_3") (pintype "bidirectional"))
      (node (ref "CN15") (pin "2") (pinfunction "DIN_2") (pintype "bidirectional"))
    )
    (net (code "31") (name "Net-(CN14-SW)") (class "Default")
      (node (ref "CN14") (pin "6") (pinfunction "SW_6") (pintype "bidirectional"))
      (node (ref "U1") (pin "18") (pinfunction "P15_18") (pintype "bidirectional"))
    )
    (net (code "32") (name "Net-(CN15-SW)") (class "Default")
      (node (ref "CN15") (pin "6") (pinfunction "SW_6") (pintype "bidirectional"))
      (node (ref "U1") (pin "19") (pinfunction "P16_19") (pintype "bidirectional"))
    )
    (net (code "33") (name "Net-(CN16-DOUT)") (class "Default")
      (node (ref "CN16") (pin "3") (pinfunction "DOUT_3") (pintype "bidirectional"))
      (node (ref "CN17") (pin "2") (pinfunction "DIN_2") (pintype "bidirectional"))
    )
    (net (code "34") (name "Net-(CN16-SW)") (class "Default")
      (node (ref "CN16") (pin "6") (pinfunction "SW_6") (pintype "bidirectional"))
      (node (ref "U2") (pin "4") (pinfunction "P00_4") (pintype "bidirectional"))
    )
    (net (code "35") (name "Net-(CN17-DOUT)") (class "Default")
      (node (ref "CN17") (pin "3") (pinfunction "DOUT_3") (pintype "bidirectional"))
      (node (ref "CN18") (pin "2") (pinfunction "DIN_2") (pintype "bidirectional"))
    )
    (net (code "36") (name "Net-(CN17-SW)") (class "Default")
      (node (ref "CN17") (pin "6") (pinfunction "SW_6") (pintype "bidirectional"))
      (node (ref "U2") (pin "5") (pinfunction "P01_5") (pintype "bidirectional"))
    )
    (net (code "37") (name "Net-(CN18-DOUT)") (class "Default")
      (node (ref "CN18") (pin "3") (pinfunction "DOUT_3") (pintype "bidirectional"))
      (node (ref "CN19") (pin "2") (pinfunction "DIN_2") (pintype "bidirectional"))
    )
    (net (code "38") (name "Net-(CN18-SW)") (class "Default")
      (node (ref "CN18") (pin "6") (pinfunction "SW_6") (pintype "bidirectional"))
      (node (ref "U2") (pin "6") (pinfunction "P02_6") (pintype "bidirectional"))
    )
    (net (code "39") (name "Net-(CN19-DOUT)") (class "Default")
      (node (ref "CN19") (pin "3") (pinfunction "DOUT_3") (pintype "bidirectional"))
      (node (ref "CN20") (pin "2") (pinfunction "DIN_2") (pintype "bidirectional"))
    )
    (net (code "40") (name "Net-(CN19-SW)") (class "Default")
      (node (ref "CN19") (pin "6") (pinfunction "SW_6") (pintype "bidirectional"))
      (node (ref "U2") (pin "7") (pinfunction "P03_7") (pintype "bidirectional"))
    )
    (net (code "41") (name "Net-(CN20-SW)") (class "Default")
      (node (ref "CN20") (pin "6") (pinfunction "SW_6") (pintype "bidirectional"))
      (node (ref "U2") (pin "8") (pinfunction "P04_8") (pintype "bidirectional"))
    )
    (net (code "42") (name "Net-(CN21-DOUT)") (class "Default")
      (node (ref "CN21") (pin "3") (pinfunction "DOUT_3") (pintype "bidirectional"))
      (node (ref "CN22") (pin "2") (pinfunction "DIN_2") (pintype "bidirectional"))
    )
    (net (code "43") (name "Net-(CN21-SW)") (class "Default")
      (node (ref "CN21") (pin "6") (pinfunction "SW_6") (pintype "bidirectional"))
      (node (ref "U2") (pin "9") (pinfunction "P05_9") (pintype "bidirectional"))
    )
    (net (code "44") (name "Net-(CN22-DOUT)") (class "Default")
      (node (ref "CN22") (pin "3") (pinfunction "DOUT_3") (pintype "bidirectional"))
      (node (ref "CN23") (pin "2") (pinfunction "DIN_2") (pintype "bidirectional"))
    )
    (net (code "45") (name "Net-(CN22-SW)") (class "Default")
      (node (ref "CN22") (pin "6") (pinfunction "SW_6") (pintype "bidirectional"))
      (node (ref "U2") (pin "10") (pinfunction "P06_10") (pintype "bidirectional"))
    )
    (net (code "46") (name "Net-(CN23-DOUT)") (class "Default")
      (node (ref "CN23") (pin "3") (pinfunction "DOUT_3") (pintype "bidirectional"))
      (node (ref "CN24") (pin "2") (pinfunction "DIN_2") (pintype "bidirectional"))
    )
    (net (code "47") (name "Net-(CN23-SW)") (class "Default")
      (node (ref "CN23") (pin "6") (pinfunction "SW_6") (pintype "bidirectional"))
      (node (ref "U2") (pin "11") (pinfunction "P07_11") (pintype "bidirectional"))
    )
    (net (code "48") (name "Net-(CN24-DOUT)") (class "Default")
      (node (ref "CN24") (pin "3") (pinfunction "DOUT_3") (pintype "bidirectional"))
      (node (ref "CN25") (pin "2") (pinfunction "DIN_2") (pintype "bidirectional"))
    )
    (net (code "49") (name "Net-(CN24-SW)") (class "Default")
      (node (ref "CN24") (pin "6") (pinfunction "SW_6") (pintype "bidirectional"))
      (node (ref "U2") (pin "13") (pinfunction "P10_13") (pintype "bidirectional"))
    )
    (net (code "50") (name "Net-(CN25-SW)") (class "Default")
      (node (ref "CN25") (pin "6") (pinfunction "SW_6") (pintype "bidirectional"))
      (node (ref "U2") (pin "14") (pinfunction "P11_14") (pintype "bidirectional"))
    )
    (net (code "51") (name "Net-(J3-EN)") (class "Default")
      (node (ref "J3") (pin "4") (pinfunction "EN_4") (pintype "bidirectional"))
      (node (ref "TP23") (pin "P$1") (pinfunction "1_P$1") (pintype "bidirectional"))
    )
    (net (code "52") (name "Net-(J4-VIN)") (class "Default")
      (node (ref "J2") (pin "2") (pinfunction "2_2") (pintype "bidirectional"))
      (node (ref "J4") (pin "3") (pinfunction "VIN_3") (pintype "bidirectional"))
      (node (ref "TP17") (pin "P$1") (pinfunction "1_P$1") (pintype "bidirectional"))
    )
    (net (code "53") (name "Net-(J4-VOUT)") (class "Default")
      (node (ref "J4") (pin "1") (pinfunction "VOUT_1") (pintype "bidirectional"))
      (node (ref "R9") (pin "2") (pinfunction "P$2_2") (pintype "bidirectional"))
      (node (ref "U4") (pin "3") (pinfunction "IN+_3") (pintype "power_in"))
    )
    (net (code "54") (name "Net-(J4-{slash}SHDN)") (class "Default")
      (node (ref "J1") (pin "2") (pinfunction "2_2") (pintype "bidirectional"))
      (node (ref "J4") (pin "4") (pinfunction "/SHDN_4") (pintype "bidirectional"))
      (node (ref "TP15") (pin "P$1") (pinfunction "1_P$1") (pintype "bidirectional"))
    )
    (net (code "55") (name "Net-(Q1-S)") (class "Default")
      (node (ref "Q1") (pin "2") (pinfunction "S_2") (pintype "bidirectional"))
      (node (ref "R3") (pin "1") (pinfunction "P$1_1") (pintype "bidirectional"))
      (node (ref "TP2") (pin "P$1") (pinfunction "1_P$1") (pintype "bidirectional"))
      (node (ref "U3") (pin "R6") (pinfunction "D11_R6") (pintype "bidirectional"))
    )
    (net (code "56") (name "Net-(Q2-S)") (class "Default")
      (node (ref "Q2") (pin "2") (pinfunction "S_2") (pintype "bidirectional"))
      (node (ref "R5") (pin "1") (pinfunction "P$1_1") (pintype "bidirectional"))
      (node (ref "TP3") (pin "P$1") (pinfunction "1_P$1") (pintype "bidirectional"))
      (node (ref "U3") (pin "R5") (pinfunction "D10_R5") (pintype "bidirectional"))
    )
    (net (code "57") (name "Net-(Q3-S)") (class "Default")
      (node (ref "Q3") (pin "2") (pinfunction "S_2") (pintype "bidirectional"))
      (node (ref "R1") (pin "1") (pinfunction "P$1_1") (pintype "bidirectional"))
      (node (ref "TP1") (pin "P$1") (pinfunction "1_P$1") (pintype "bidirectional"))
      (node (ref "U3") (pin "R7") (pinfunction "D12_R7") (pintype "bidirectional"))
    )
    (net (code "58") (name "Net-(Q4-S)") (class "Default")
      (node (ref "Q4") (pin "2") (pinfunction "S_2") (pintype "bidirectional"))
      (node (ref "R7") (pin "1") (pinfunction "P$1_1") (pintype "bidirectional"))
      (node (ref "TP4") (pin "P$1") (pinfunction "1_P$1") (pintype "bidirectional"))
      (node (ref "U3") (pin "R1") (pinfunction "D6_R1") (pintype "bidirectional"))
    )
    (net (code "59") (name "ROW1DOUT") (class "Default")
      (node (ref "CN5") (pin "3") (pinfunction "DOUT_3") (pintype "bidirectional"))
      (node (ref "CN6") (pin "2") (pinfunction "DIN_2") (pintype "bidirectional"))
      (node (ref "TP9") (pin "P$1") (pinfunction "1_P$1") (pintype "bidirectional"))
    )
    (net (code "60") (name "ROW2DOUT") (class "Default")
      (node (ref "CN10") (pin "3") (pinfunction "DOUT_3") (pintype "bidirectional"))
      (node (ref "CN11") (pin "2") (pinfunction "DIN_2") (pintype "bidirectional"))
      (node (ref "TP10") (pin "P$1") (pinfunction "1_P$1") (pintype "bidirectional"))
    )
    (net (code "61") (name "ROW3DOUT") (class "Default")
      (node (ref "CN15") (pin "3") (pinfunction "DOUT_3") (pintype "bidirectional"))
      (node (ref "CN16") (pin "2") (pinfunction "DIN_2") (pintype "bidirectional"))
      (node (ref "TP11") (pin "P$1") (pinfunction "1_P$1") (pintype "bidirectional"))
    )
    (net (code "62") (name "ROW4DOUT") (class "Default")
      (node (ref "CN20") (pin "3") (pinfunction "DOUT_3") (pintype "bidirectional"))
      (node (ref "CN21") (pin "2") (pinfunction "DIN_2") (pintype "bidirectional"))
      (node (ref "TP12") (pin "P$1") (pinfunction "1_P$1") (pintype "bidirectional"))
    )
    (net (code "63") (name "ROW5DOUT") (class "Default")
      (node (ref "CN25") (pin "3") (pinfunction "DOUT_3") (pintype "bidirectional"))
      (node (ref "TP13") (pin "P$1") (pinfunction "1_P$1") (pintype "bidirectional"))
    )
    (net (code "64") (name "SCL") (class "Default")
      (node (ref "Q3") (pin "3") (pinfunction "D_3") (pintype "bidirectional"))
      (node (ref "R2") (pin "1") (pinfunction "P$1_1") (pintype "bidirectional"))
      (node (ref "TP5") (pin "P$1") (pinfunction "1_P$1") (pintype "bidirectional"))
      (node (ref "U1") (pin "22") (pinfunction "SCL_22") (pintype "bidirectional"))
      (node (ref "U2") (pin "22") (pinfunction "SCL_22") (pintype "bidirectional"))
    )
    (net (code "65") (name "SDA") (class "Default")
      (node (ref "Q1") (pin "3") (pinfunction "D_3") (pintype "bidirectional"))
      (node (ref "R4") (pin "1") (pinfunction "P$1_1") (pintype "bidirectional"))
      (node (ref "TP6") (pin "P$1") (pinfunction "1_P$1") (pintype "bidirectional"))
      (node (ref "U1") (pin "23") (pinfunction "SDA_23") (pintype "bidirectional"))
      (node (ref "U2") (pin "23") (pinfunction "SDA_23") (pintype "bidirectional"))
    )
    (net (code "66") (name "unconnected-(U1-P17-Pad20)") (class "Default")
      (node (ref "U1") (pin "20") (pinfunction "P17_20") (pintype "bidirectional"))
    )
    (net (code "67") (name "unconnected-(U2-P12-Pad15)") (class "Default")
      (node (ref "U2") (pin "15") (pinfunction "P12_15") (pintype "bidirectional"))
    )
    (net (code "68") (name "unconnected-(U2-P13-Pad16)") (class "Default")
      (node (ref "U2") (pin "16") (pinfunction "P13_16") (pintype "bidirectional"))
    )
    (net (code "69") (name "unconnected-(U2-P14-Pad17)") (class "Default")
      (node (ref "U2") (pin "17") (pinfunction "P14_17") (pintype "bidirectional"))
    )
    (net (code "70") (name "unconnected-(U2-P15-Pad18)") (class "Default")
      (node (ref "U2") (pin "18") (pinfunction "P15_18") (pintype "bidirectional"))
    )
    (net (code "71") (name "unconnected-(U2-P16-Pad19)") (class "Default")
      (node (ref "U2") (pin "19") (pinfunction "P16_19") (pintype "bidirectional"))
    )
    (net (code "72") (name "unconnected-(U2-P17-Pad20)") (class "Default")
      (node (ref "U2") (pin "20") (pinfunction "P17_20") (pintype "bidirectional"))
    )
    (net (code "73") (name "unconnected-(U3-A1-PadL3)") (class "Default")
      (node (ref "U3") (pin "L3") (pinfunction "A1_L3") (pintype "bidirectional"))
    )
    (net (code "74") (name "unconnected-(U3-A2-PadL4)") (class "Default")
      (node (ref "U3") (pin "L4") (pinfunction "A2_L4") (pintype "bidirectional"))
    )
    (net (code "75") (name "unconnected-(U3-A3-PadL5)") (class "Default")
      (node (ref "U3") (pin "L5") (pinfunction "A3_L5") (pintype "bidirectional"))
    )
    (net (code "76") (name "unconnected-(U3-A4-PadL6)") (class "Default")
      (node (ref "U3") (pin "L6") (pinfunction "A4_L6") (pintype "bidirectional"))
    )
    (net (code "77") (name "unconnected-(U3-A5-PadL7)") (class "Default")
      (node (ref "U3") (pin "L7") (pinfunction "A5_L7") (pintype "bidirectional"))
    )
    (net (code "78") (name "unconnected-(U3-A6-PadL8)") (class "Default")
      (node (ref "U3") (pin "L8") (pinfunction "A6_L8") (pintype "bidirectional"))
    )
    (net (code "79") (name "unconnected-(U3-AREF-PadL1)") (class "Default")
      (node (ref "U3") (pin "L1") (pinfunction "AREF_L1") (pintype "bidirectional"))
    )
    (net (code "80") (name "unconnected-(U3-D0-PadL9)") (class "Default")
      (node (ref "U3") (pin "L9") (pinfunction "D0_L9") (pintype "bidirectional"))
    )
    (net (code "81") (name "unconnected-(U3-D1-PadL10)") (class "Default")
      (node (ref "U3") (pin "L10") (pinfunction "D1_L10") (pintype "bidirectional"))
    )
    (net (code "82") (name "unconnected-(U3-D2-PadL11)") (class "Default")
      (node (ref "U3") (pin "L11") (pinfunction "D2_L11") (pintype "bidirectional"))
    )
    (net (code "83") (name "unconnected-(U3-D3-PadL12)") (class "Default")
      (node (ref "U3") (pin "L12") (pinfunction "D3_L12") (pintype "bidirectional"))
    )
    (net (code "84") (name "unconnected-(U3-D4-PadL13)") (class "Default")
      (node (ref "U3") (pin "L13") (pinfunction "D4_L13") (pintype "bidirectional"))
    )
    (net (code "85") (name "unconnected-(U3-D5-PadL14)") (class "Default")
      (node (ref "U3") (pin "L14") (pinfunction "D5_L14") (pintype "bidirectional"))
    )
    (net (code "86") (name "unconnected-(U3-D7-PadR2)") (class "Default")
      (node (ref "U3") (pin "R2") (pinfunction "D7_R2") (pintype "bidirectional"))
    )
    (net (code "87") (name "unconnected-(U3-D8-PadR3)") (class "Default")
      (node (ref "U3") (pin "R3") (pinfunction "D8_R3") (pintype "bidirectional"))
    )
    (net (code "88") (name "unconnected-(U3-D9-PadR4)") (class "Default")
      (node (ref "U3") (pin "R4") (pinfunction "D9_R4") (pintype "bidirectional"))
    )
    (net (code "89") (name "unconnected-(U3-D13-PadR8)") (class "Default")
      (node (ref "U3") (pin "R8") (pinfunction "D13_R8") (pintype "bidirectional"))
    )
    (net (code "90") (name "unconnected-(U3-D14-PadR9)") (class "Default")
      (node (ref "U3") (pin "R9") (pinfunction "D14_R9") (pintype "bidirectional"))
    )
    (net (code "91") (name "unconnected-(U3-RESET-PadR10)") (class "Default")
      (node (ref "U3") (pin "R10") (pinfunction "RESET_R10") (pintype "bidirectional"))
    )
    (net (code "92") (name "unconnected-(U3-VCC-PadR12)") (class "Default")
      (node (ref "U3") (pin "R12") (pinfunction "VCC_R12") (pintype "bidirectional"))
    )
    (net (code "93") (name "unconnected-(U3-VIN-PadR13)") (class "Default")
      (node (ref "U3") (pin "R13") (pinfunction "VIN_R13") (pintype "bidirectional"))
    )
    (net (code "94") (name "{slash}INT") (class "Default")
      (node (ref "Q2") (pin "3") (pinfunction "D_3") (pintype "bidirectional"))
      (node (ref "R6") (pin "1") (pinfunction "P$1_1") (pintype "bidirectional"))
      (node (ref "TP7") (pin "P$1") (pinfunction "1_P$1") (pintype "bidirectional"))
      (node (ref "U1") (pin "1") (pinfunction "/INT_1") (pintype "bidirectional"))
      (node (ref "U2") (pin "1") (pinfunction "/INT_1") (pintype "bidirectional"))
    )
  )
)
